# Ethernet.net
KiCad netlist of a schematic drawn in Altium Designer
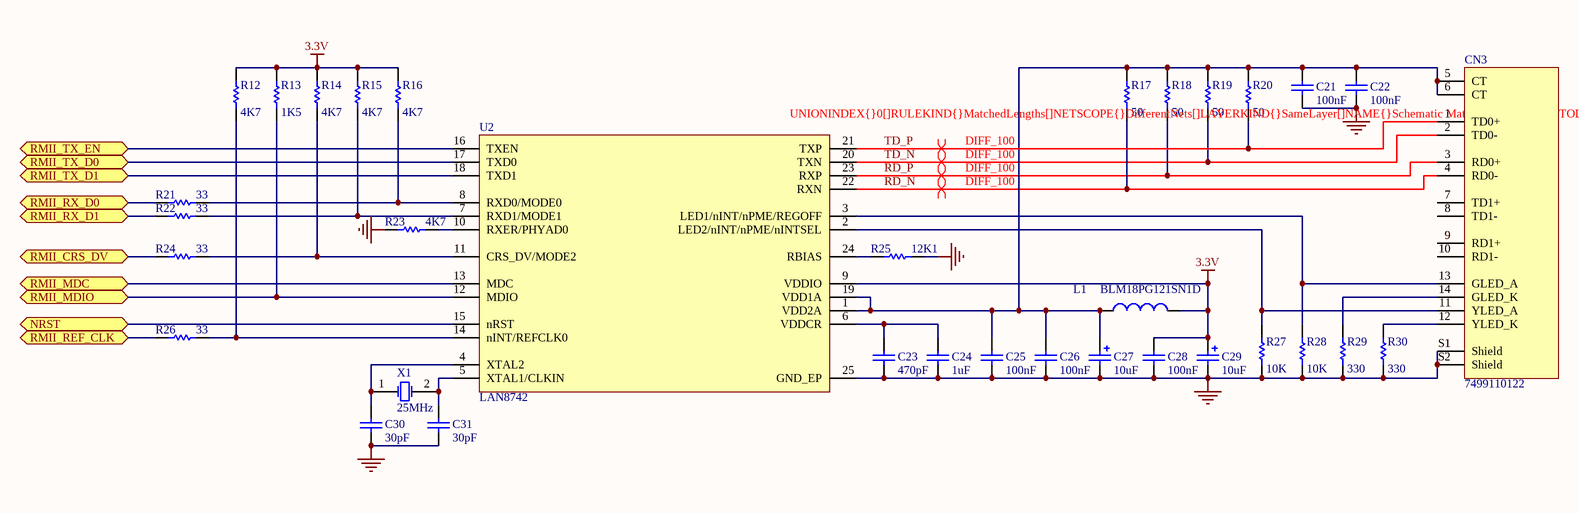
[diagram p0: Ethernet.SchDoc]

(export (version "E")
  (design (tool "Eeschema 10.0.6"))
  (components
    (comp (ref "C21")
      (value "100nF")
      (footprint "CAPC2012N")
      (description "Capacitor")
      (fields (field (name "Comment") "Cap"))
      (libsource (lib "Core429IBaseBoard") (part "Cap"))
    )
    (comp (ref "C22")
      (value "100nF")
      (footprint "CAPC2012N")
      (description "Capacitor")
      (fields (field (name "Comment") "Cap"))
      (libsource (lib "Core429IBaseBoard") (part "Cap"))
    )
    (comp (ref "C23")
      (value "470pF")
      (footprint "CAPC2012N")
      (description "Capacitor")
      (fields (field (name "Comment") "Cap"))
      (libsource (lib "Core429IBaseBoard") (part "Cap"))
    )
    (comp (ref "C24")
      (value "1uF")
      (footprint "CAPC3216N")
      (description "Capacitor")
      (fields (field (name "Comment") "Cap"))
      (libsource (lib "Core429IBaseBoard") (part "Cap"))
    )
    (comp (ref "C25")
      (value "100nF")
      (footprint "CAPC2012N")
      (description "Capacitor")
      (fields (field (name "Comment") "Cap"))
      (libsource (lib "Core429IBaseBoard") (part "Cap"))
    )
    (comp (ref "C26")
      (value "100nF")
      (footprint "CAPC2012N")
      (description "Capacitor")
      (fields (field (name "Comment") "Cap"))
      (libsource (lib "Core429IBaseBoard") (part "Cap"))
    )
    (comp (ref "C27")
      (value "10uF")
      (footprint "TC3216-1206")
      (description "Polarized Capacitor")
      (fields (field (name "Comment") "Cap Pol"))
      (libsource (lib "Core429IBaseBoard") (part "Cap Pol"))
    )
    (comp (ref "C28")
      (value "100nF")
      (footprint "CAPC2012N")
      (description "Capacitor")
      (fields (field (name "Comment") "Cap"))
      (libsource (lib "Core429IBaseBoard") (part "Cap"))
    )
    (comp (ref "C29")
      (value "10uF")
      (footprint "TC3216-1206")
      (description "Polarized Capacitor")
      (fields (field (name "Comment") "Cap Pol"))
      (libsource (lib "Core429IBaseBoard") (part "Cap Pol"))
    )
    (comp (ref "C30")
      (value "30pF")
      (footprint "CAPC2012N")
      (description "Capacitor")
      (fields (field (name "Comment") "Cap"))
      (libsource (lib "Core429IBaseBoard") (part "Cap"))
    )
    (comp (ref "C31")
      (value "30pF")
      (footprint "CAPC2012N")
      (description "Capacitor")
      (fields (field (name "Comment") "Cap"))
      (libsource (lib "Core429IBaseBoard") (part "Cap"))
    )
    (comp (ref "CN3")
      (value "7499110122")
      (footprint "7499110122")
      (description "LAN-Transformer WE-RJ45LAN 10/100/1000 BaseT")
      (libsource (lib "Core429IBaseBoardVerF") (part "7499110122"))
    )
    (comp (ref "L1")
      (value "BLM18PG121SN1D")
      (footprint "INDC2012N")
      (description "Inductor")
      (libsource (lib "Core429IBaseBoard") (part "Inductor"))
    )
    (comp (ref "R12")
      (value "4K7")
      (footprint "RESC2012N")
      (description "Resistor")
      (fields (field (name "Comment") "1206"))
      (libsource (lib "Core429IBaseBoard") (part "Res"))
    )
    (comp (ref "R13")
      (value "1K5")
      (footprint "RESC2012N")
      (description "Resistor")
      (fields (field (name "Comment") "1206"))
      (libsource (lib "Core429IBaseBoard") (part "Res"))
    )
    (comp (ref "R14")
      (value "4K7")
      (footprint "RESC2012N")
      (description "Resistor")
      (fields (field (name "Comment") "1206"))
      (libsource (lib "Core429IBaseBoard") (part "Res"))
    )
    (comp (ref "R15")
      (value "4K7")
      (footprint "RESC2012N")
      (description "Resistor")
      (fields (field (name "Comment") "1206"))
      (libsource (lib "Core429IBaseBoard") (part "Res"))
    )
    (comp (ref "R16")
      (value "4K7")
      (footprint "RESC2012N")
      (description "Resistor")
      (fields (field (name "Comment") "1206"))
      (libsource (lib "Core429IBaseBoard") (part "Res"))
    )
    (comp (ref "R17")
      (value "50")
      (footprint "RESC2012N")
      (description "Resistor")
      (fields (field (name "Comment") "1206"))
      (libsource (lib "Core429IBaseBoard") (part "Res"))
    )
    (comp (ref "R18")
      (value "50")
      (footprint "RESC2012N")
      (description "Resistor")
      (fields (field (name "Comment") "1206"))
      (libsource (lib "Core429IBaseBoard") (part "Res"))
    )
    (comp (ref "R19")
      (value "50")
      (footprint "RESC2012N")
      (description "Resistor")
      (fields (field (name "Comment") "1206"))
      (libsource (lib "Core429IBaseBoard") (part "Res"))
    )
    (comp (ref "R20")
      (value "50")
      (footprint "RESC2012N")
      (description "Resistor")
      (fields (field (name "Comment") "1206"))
      (libsource (lib "Core429IBaseBoard") (part "Res"))
    )
    (comp (ref "R21")
      (value "33")
      (footprint "RESC2012N")
      (description "Resistor")
      (fields (field (name "Comment") "1206"))
      (libsource (lib "Core429IBaseBoard") (part "Res"))
    )
    (comp (ref "R22")
      (value "33")
      (footprint "RESC2012N")
      (description "Resistor")
      (fields (field (name "Comment") "1206"))
      (libsource (lib "Core429IBaseBoard") (part "Res"))
    )
    (comp (ref "R23")
      (value "4K7")
      (footprint "RESC2012N")
      (description "Resistor")
      (fields (field (name "Comment") "1206"))
      (libsource (lib "Core429IBaseBoard") (part "Res"))
    )
    (comp (ref "R24")
      (value "33")
      (footprint "RESC2012N")
      (description "Resistor")
      (fields (field (name "Comment") "1206"))
      (libsource (lib "Core429IBaseBoard") (part "Res"))
    )
    (comp (ref "R25")
      (value "12K1")
      (footprint "RESC2012N")
      (description "Resistor")
      (fields (field (name "Comment") "1206"))
      (libsource (lib "Core429IBaseBoard") (part "Res"))
    )
    (comp (ref "R26")
      (value "33")
      (footprint "RESC2012N")
      (description "Resistor")
      (fields (field (name "Comment") "1206"))
      (libsource (lib "Core429IBaseBoard") (part "Res"))
    )
    (comp (ref "R27")
      (value "10K")
      (footprint "RESC2012N")
      (description "Resistor")
      (fields (field (name "Comment") "1206"))
      (libsource (lib "Core429IBaseBoard") (part "Res"))
    )
    (comp (ref "R28")
      (value "10K")
      (footprint "RESC2012N")
      (description "Resistor")
      (fields (field (name "Comment") "1206"))
      (libsource (lib "Core429IBaseBoard") (part "Res"))
    )
    (comp (ref "R29")
      (value "330")
      (footprint "RESC2012N")
      (description "Resistor")
      (fields (field (name "Comment") "1206"))
      (libsource (lib "Core429IBaseBoard") (part "Res"))
    )
    (comp (ref "R30")
      (value "330")
      (footprint "RESC2012N")
      (description "Resistor")
      (fields (field (name "Comment") "1206"))
      (libsource (lib "Core429IBaseBoard") (part "Res"))
    )
    (comp (ref "U2")
      (value "LAN8742")
      (footprint "QFN50P400X400X100-24M")
      (description "Small Footprint RMII 10/100 Ethernet Transceiver with HP Auto-MDIX and flexPWR Technology")
      (libsource (lib "Core429IBaseBoard") (part "LAN8742"))
    )
    (comp (ref "X1")
      (value "25MHz")
      (footprint "QC5CB")
      (description "Crystal Oscillator")
      (libsource (lib "Core429IBaseBoard") (part "XTAL"))
    )
  )
  (nets
    (net (code "1") (name "/NRST") (class "Default")
      (node (ref "U2") (pin "15") (pinfunction "nRST_15") (pintype "passive"))
    )
    (net (code "2") (name "/RD_N") (class "Default")
      (node (ref "CN3") (pin "4") (pinfunction "RD0-_4") (pintype "passive"))
      (node (ref "R17") (pin "1") (pinfunction "1_1") (pintype "passive"))
      (node (ref "U2") (pin "22") (pinfunction "RXN_22") (pintype "passive"))
    )
    (net (code "3") (name "/RD_P") (class "Default")
      (node (ref "CN3") (pin "3") (pinfunction "RD0+_3") (pintype "passive"))
      (node (ref "R18") (pin "1") (pinfunction "1_1") (pintype "passive"))
      (node (ref "U2") (pin "23") (pinfunction "RXP_23") (pintype "passive"))
    )
    (net (code "4") (name "/RMII_CRS_DV") (class "Default")
      (node (ref "R24") (pin "2") (pinfunction "2_2") (pintype "passive"))
    )
    (net (code "5") (name "/RMII_MDC") (class "Default")
      (node (ref "U2") (pin "13") (pinfunction "MDC_13") (pintype "passive"))
    )
    (net (code "6") (name "/RMII_MDIO") (class "Default")
      (node (ref "R13") (pin "1") (pinfunction "1_1") (pintype "passive"))
      (node (ref "U2") (pin "12") (pinfunction "MDIO_12") (pintype "passive"))
    )
    (net (code "7") (name "/RMII_REF_CLK") (class "Default")
      (node (ref "R26") (pin "2") (pinfunction "2_2") (pintype "passive"))
    )
    (net (code "8") (name "/RMII_RX_D0") (class "Default")
      (node (ref "R21") (pin "2") (pinfunction "2_2") (pintype "passive"))
    )
    (net (code "9") (name "/RMII_RX_D1") (class "Default")
      (node (ref "R22") (pin "2") (pinfunction "2_2") (pintype "passive"))
    )
    (net (code "10") (name "/RMII_TX_D0") (class "Default")
      (node (ref "U2") (pin "17") (pinfunction "TXD0_17") (pintype "passive"))
    )
    (net (code "11") (name "/RMII_TX_D1") (class "Default")
      (node (ref "U2") (pin "18") (pinfunction "TXD1_18") (pintype "passive"))
    )
    (net (code "12") (name "/RMII_TX_EN") (class "Default")
      (node (ref "U2") (pin "16") (pinfunction "TXEN_16") (pintype "passive"))
    )
    (net (code "13") (name "/TD_N") (class "Default")
      (node (ref "CN3") (pin "2") (pinfunction "TD0-_2") (pintype "passive"))
      (node (ref "R19") (pin "1") (pinfunction "1_1") (pintype "passive"))
      (node (ref "U2") (pin "20") (pinfunction "TXN_20") (pintype "passive"))
    )
    (net (code "14") (name "/TD_P") (class "Default")
      (node (ref "CN3") (pin "1") (pinfunction "TD0+_1") (pintype "passive"))
      (node (ref "R20") (pin "1") (pinfunction "1_1") (pintype "passive"))
      (node (ref "U2") (pin "21") (pinfunction "TXP_21") (pintype "passive"))
    )
    (net (code "15") (name "3.3V") (class "Default")
      (node (ref "C28") (pin "2") (pinfunction "2_2") (pintype "passive"))
      (node (ref "C29") (pin "1") (pinfunction "1_1") (pintype "passive"))
      (node (ref "L1") (pin "2") (pinfunction "2_2") (pintype "passive"))
      (node (ref "R12") (pin "2") (pinfunction "2_2") (pintype "passive"))
      (node (ref "R13") (pin "2") (pinfunction "2_2") (pintype "passive"))
      (node (ref "R14") (pin "2") (pinfunction "2_2") (pintype "passive"))
      (node (ref "R15") (pin "2") (pinfunction "2_2") (pintype "passive"))
      (node (ref "R16") (pin "2") (pinfunction "2_2") (pintype "passive"))
      (node (ref "U2") (pin "9") (pinfunction "VDDIO_9") (pintype "passive"))
    )
    (net (code "16") (name "DGND") (class "Default")
      (node (ref "C21") (pin "1") (pinfunction "1_1") (pintype "passive"))
      (node (ref "C22") (pin "1") (pinfunction "1_1") (pintype "passive"))
      (node (ref "C23") (pin "1") (pinfunction "1_1") (pintype "passive"))
      (node (ref "C24") (pin "1") (pinfunction "1_1") (pintype "passive"))
      (node (ref "C25") (pin "1") (pinfunction "1_1") (pintype "passive"))
      (node (ref "C26") (pin "1") (pinfunction "1_1") (pintype "passive"))
      (node (ref "C27") (pin "2") (pinfunction "2_2") (pintype "passive"))
      (node (ref "C28") (pin "1") (pinfunction "1_1") (pintype "passive"))
      (node (ref "C29") (pin "2") (pinfunction "2_2") (pintype "passive"))
      (node (ref "C30") (pin "1") (pinfunction "1_1") (pintype "passive"))
      (node (ref "C31") (pin "1") (pinfunction "1_1") (pintype "passive"))
      (node (ref "CN3") (pin "S1") (pinfunction "Shield_S1") (pintype "passive"))
      (node (ref "CN3") (pin "S2") (pinfunction "Shield_S2") (pintype "passive"))
      (node (ref "R23") (pin "2") (pinfunction "2_2") (pintype "passive"))
      (node (ref "R25") (pin "1") (pinfunction "1_1") (pintype "passive"))
      (node (ref "R27") (pin "1") (pinfunction "1_1") (pintype "passive"))
      (node (ref "R28") (pin "1") (pinfunction "1_1") (pintype "passive"))
      (node (ref "R29") (pin "1") (pinfunction "1_1") (pintype "passive"))
      (node (ref "R30") (pin "1") (pinfunction "1_1") (pintype "passive"))
      (node (ref "U2") (pin "25") (pinfunction "GND_EP_25") (pintype "passive"))
    )
    (net (code "17") (name "Net-(CN3-GLED_A)") (class "Default")
      (node (ref "CN3") (pin "13") (pinfunction "GLED_A_13") (pintype "passive"))
      (node (ref "R28") (pin "2") (pinfunction "2_2") (pintype "passive"))
      (node (ref "U2") (pin "3") (pinfunction "LED1/nINT/nPME/REGOFF_3") (pintype "passive"))
    )
    (net (code "18") (name "Net-(CN3-GLED_K)") (class "Default")
      (node (ref "CN3") (pin "14") (pinfunction "GLED_K_14") (pintype "passive"))
      (node (ref "R29") (pin "2") (pinfunction "2_2") (pintype "passive"))
    )
    (net (code "19") (name "Net-(CN3-YLED_A)") (class "Default")
      (node (ref "CN3") (pin "11") (pinfunction "YLED_A_11") (pintype "passive"))
      (node (ref "R27") (pin "2") (pinfunction "2_2") (pintype "passive"))
      (node (ref "U2") (pin "2") (pinfunction "LED2/nINT/nPME/nINTSEL_2") (pintype "passive"))
    )
    (net (code "20") (name "Net-(CN3-YLED_K)") (class "Default")
      (node (ref "CN3") (pin "12") (pinfunction "YLED_K_12") (pintype "passive"))
      (node (ref "R30") (pin "2") (pinfunction "2_2") (pintype "passive"))
    )
    (net (code "21") (name "Net-(U2-CRS_DV{slash}MODE2)") (class "Default")
      (node (ref "R14") (pin "1") (pinfunction "1_1") (pintype "passive"))
      (node (ref "R24") (pin "1") (pinfunction "1_1") (pintype "passive"))
      (node (ref "U2") (pin "11") (pinfunction "CRS_DV/MODE2_11") (pintype "passive"))
    )
    (net (code "22") (name "Net-(U2-RBIAS)") (class "Default")
      (node (ref "R25") (pin "2") (pinfunction "2_2") (pintype "passive"))
      (node (ref "U2") (pin "24") (pinfunction "RBIAS_24") (pintype "passive"))
    )
    (net (code "23") (name "Net-(U2-RXD0{slash}MODE0)") (class "Default")
      (node (ref "R16") (pin "1") (pinfunction "1_1") (pintype "passive"))
      (node (ref "R21") (pin "1") (pinfunction "1_1") (pintype "passive"))
      (node (ref "U2") (pin "8") (pinfunction "RXD0/MODE0_8") (pintype "passive"))
    )
    (net (code "24") (name "Net-(U2-RXD1{slash}MODE1)") (class "Default")
      (node (ref "R15") (pin "1") (pinfunction "1_1") (pintype "passive"))
      (node (ref "R22") (pin "1") (pinfunction "1_1") (pintype "passive"))
      (node (ref "U2") (pin "7") (pinfunction "RXD1/MODE1_7") (pintype "passive"))
    )
    (net (code "25") (name "Net-(U2-RXER{slash}PHYAD0)") (class "Default")
      (node (ref "R23") (pin "1") (pinfunction "1_1") (pintype "passive"))
      (node (ref "U2") (pin "10") (pinfunction "RXER/PHYAD0_10") (pintype "passive"))
    )
    (net (code "26") (name "Net-(U2-VDD1A)") (class "Default")
      (node (ref "C21") (pin "2") (pinfunction "2_2") (pintype "passive"))
      (node (ref "C22") (pin "2") (pinfunction "2_2") (pintype "passive"))
      (node (ref "C25") (pin "2") (pinfunction "2_2") (pintype "passive"))
      (node (ref "C26") (pin "2") (pinfunction "2_2") (pintype "passive"))
      (node (ref "C27") (pin "1") (pinfunction "1_1") (pintype "passive"))
      (node (ref "CN3") (pin "5") (pinfunction "CT_5") (pintype "passive"))
      (node (ref "CN3") (pin "6") (pinfunction "CT_6") (pintype "passive"))
      (node (ref "L1") (pin "1") (pinfunction "1_1") (pintype "passive"))
      (node (ref "R17") (pin "2") (pinfunction "2_2") (pintype "passive"))
      (node (ref "R18") (pin "2") (pinfunction "2_2") (pintype "passive"))
      (node (ref "R19") (pin "2") (pinfunction "2_2") (pintype "passive"))
      (node (ref "R20") (pin "2") (pinfunction "2_2") (pintype "passive"))
      (node (ref "U2") (pin "1") (pinfunction "VDD2A_1") (pintype "passive"))
      (node (ref "U2") (pin "19") (pinfunction "VDD1A_19") (pintype "passive"))
    )
    (net (code "27") (name "Net-(U2-VDDCR)") (class "Default")
      (node (ref "C23") (pin "2") (pinfunction "2_2") (pintype "passive"))
      (node (ref "C24") (pin "2") (pinfunction "2_2") (pintype "passive"))
      (node (ref "U2") (pin "6") (pinfunction "VDDCR_6") (pintype "passive"))
    )
    (net (code "28") (name "Net-(U2-XTAL1{slash}CLKIN)") (class "Default")
      (node (ref "C31") (pin "2") (pinfunction "2_2") (pintype "passive"))
      (node (ref "U2") (pin "5") (pinfunction "XTAL1/CLKIN_5") (pintype "passive"))
      (node (ref "X1") (pin "2") (pinfunction "OSC2_2") (pintype "passive"))
    )
    (net (code "29") (name "Net-(U2-XTAL2)") (class "Default")
      (node (ref "C30") (pin "2") (pinfunction "2_2") (pintype "passive"))
      (node (ref "U2") (pin "4") (pinfunction "XTAL2_4") (pintype "passive"))
      (node (ref "X1") (pin "1") (pinfunction "OSC1_1") (pintype "passive"))
    )
    (net (code "30") (name "Net-(U2-nINT{slash}REFCLK0)") (class "Default")
      (node (ref "R12") (pin "1") (pinfunction "1_1") (pintype "passive"))
      (node (ref "R26") (pin "1") (pinfunction "1_1") (pintype "passive"))
      (node (ref "U2") (pin "14") (pinfunction "nINT/REFCLK0_14") (pintype "passive"))
    )
    (net (code "31") (name "unconnected-(CN3-RD1+-Pad9)") (class "Default")
      (node (ref "CN3") (pin "9") (pinfunction "RD1+_9") (pintype "passive"))
    )
    (net (code "32") (name "unconnected-(CN3-RD1--Pad10)") (class "Default")
      (node (ref "CN3") (pin "10") (pinfunction "RD1-_10") (pintype "passive"))
    )
    (net (code "33") (name "unconnected-(CN3-TD1+-Pad7)") (class "Default")
      (node (ref "CN3") (pin "7") (pinfunction "TD1+_7") (pintype "passive"))
    )
    (net (code "34") (name "unconnected-(CN3-TD1--Pad8)") (class "Default")
      (node (ref "CN3") (pin "8") (pinfunction "TD1-_8") (pintype "passive"))
    )
  )
)
